# design.net
KiCad netlist of a schematic drawn in Altium Designer
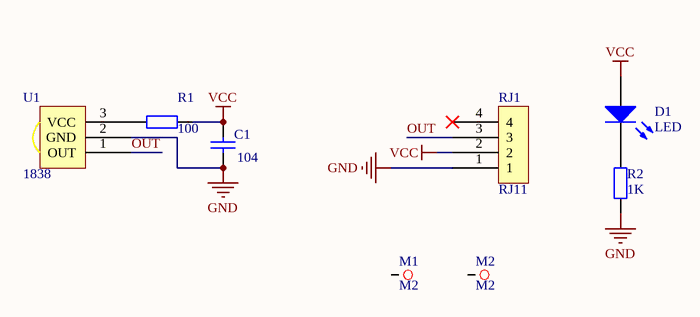
[diagram p0: 红外解码.SchDoc]

(export (version "E")
  (design (tool "Eeschema 10.0.6"))
  (components
    (comp (ref "C1")
      (value "104")
      (footprint "0603_C")
      (description "Capacitor")
      (fields (field (name "Comment") "Cap") (field (name "PUBLISHER") "Altium Limited"))
      (libsource (lib "Miscellaneous Devices") (part "Cap"))
    )
    (comp (ref "D1")
      (value "LED")
      (footprint "0805")
      (description "Typical RED GaAs LED")
      (fields (field (name "PUBLISHER") "Altium Limited"))
      (libsource (lib "Miscellaneous Devices") (part "LED1"))
    )
    (comp (ref "M1") (value "M2") (footprint "M2") (libsource (lib "QQW-1.SCHLIB") (part "M3")))
    (comp (ref "M2") (value "M2") (footprint "M2") (libsource (lib "QQW-1.SCHLIB") (part "M3")))
    (comp (ref "R1")
      (value "100")
      (footprint "0603_R")
      (description "Resistor")
      (fields (field (name "Comment") "Res2") (field (name "PUBLISHER") "Altium Limited"))
      (libsource (lib "Miscellaneous Devices") (part "Res2"))
    )
    (comp (ref "R2")
      (value "1K")
      (footprint "0603_R")
      (description "Resistor")
      (fields (field (name "Comment") "Res2") (field (name "PUBLISHER") "Altium Limited"))
      (libsource (lib "") (part "Res2_1"))
    )
    (comp (ref "RJ1") (value "RJ11") (footprint "RJ11") (libsource (lib "少儿智能车") (part "RJ11")))
    (comp (ref "U1") (value "1838") (footprint "1838") (libsource (lib "红外解码") (part "1838")))
  )
  (nets
    (net (code "1") (name "/OUT") (class "Default")
      (node (ref "RJ1") (pin "3") (pinfunction "3_3") (pintype "passive"))
      (node (ref "U1") (pin "1") (pinfunction "OUT_1") (pintype "passive"))
    )
    (net (code "2") (name "GND") (class "Default")
      (node (ref "C1") (pin "1") (pinfunction "1_1") (pintype "passive"))
      (node (ref "R2") (pin "1") (pinfunction "1_1") (pintype "passive"))
      (node (ref "RJ1") (pin "1") (pinfunction "1_1") (pintype "passive"))
      (node (ref "U1") (pin "2") (pinfunction "GND_2") (pintype "passive"))
    )
    (net (code "3") (name "Net-(D1-K)") (class "Default")
      (node (ref "D1") (pin "2") (pinfunction "K_2") (pintype "passive"))
      (node (ref "R2") (pin "2") (pinfunction "2_2") (pintype "passive"))
    )
    (net (code "4") (name "Net-(U1-VCC)") (class "Default")
      (node (ref "R1") (pin "1") (pinfunction "1_1") (pintype "passive"))
      (node (ref "U1") (pin "3") (pinfunction "VCC_3") (pintype "passive"))
    )
    (net (code "5") (name "VCC") (class "Default")
      (node (ref "C1") (pin "2") (pinfunction "2_2") (pintype "passive"))
      (node (ref "D1") (pin "1") (pinfunction "A_1") (pintype "passive"))
      (node (ref "R1") (pin "2") (pinfunction "2_2") (pintype "passive"))
      (node (ref "RJ1") (pin "2") (pinfunction "2_2") (pintype "passive"))
    )
    (net (code "6") (name "unconnected-(M1-Pad0)") (class "Default")
      (node (ref "M1") (pin "0") (pinfunction "0_0") (pintype "passive"))
    )
    (net (code "7") (name "unconnected-(M2-Pad0)") (class "Default")
      (node (ref "M2") (pin "0") (pinfunction "0_0") (pintype "passive"))
    )
    (net (code "8") (name "unconnected-(RJ1-Pad4)") (class "Default")
      (node (ref "RJ1") (pin "4") (pinfunction "4_4") (pintype "passive+no_connect"))
    )
  )
)
